# SmartUrometer_Schematic.net
KiCad netlist of a schematic drawn in Altium Designer
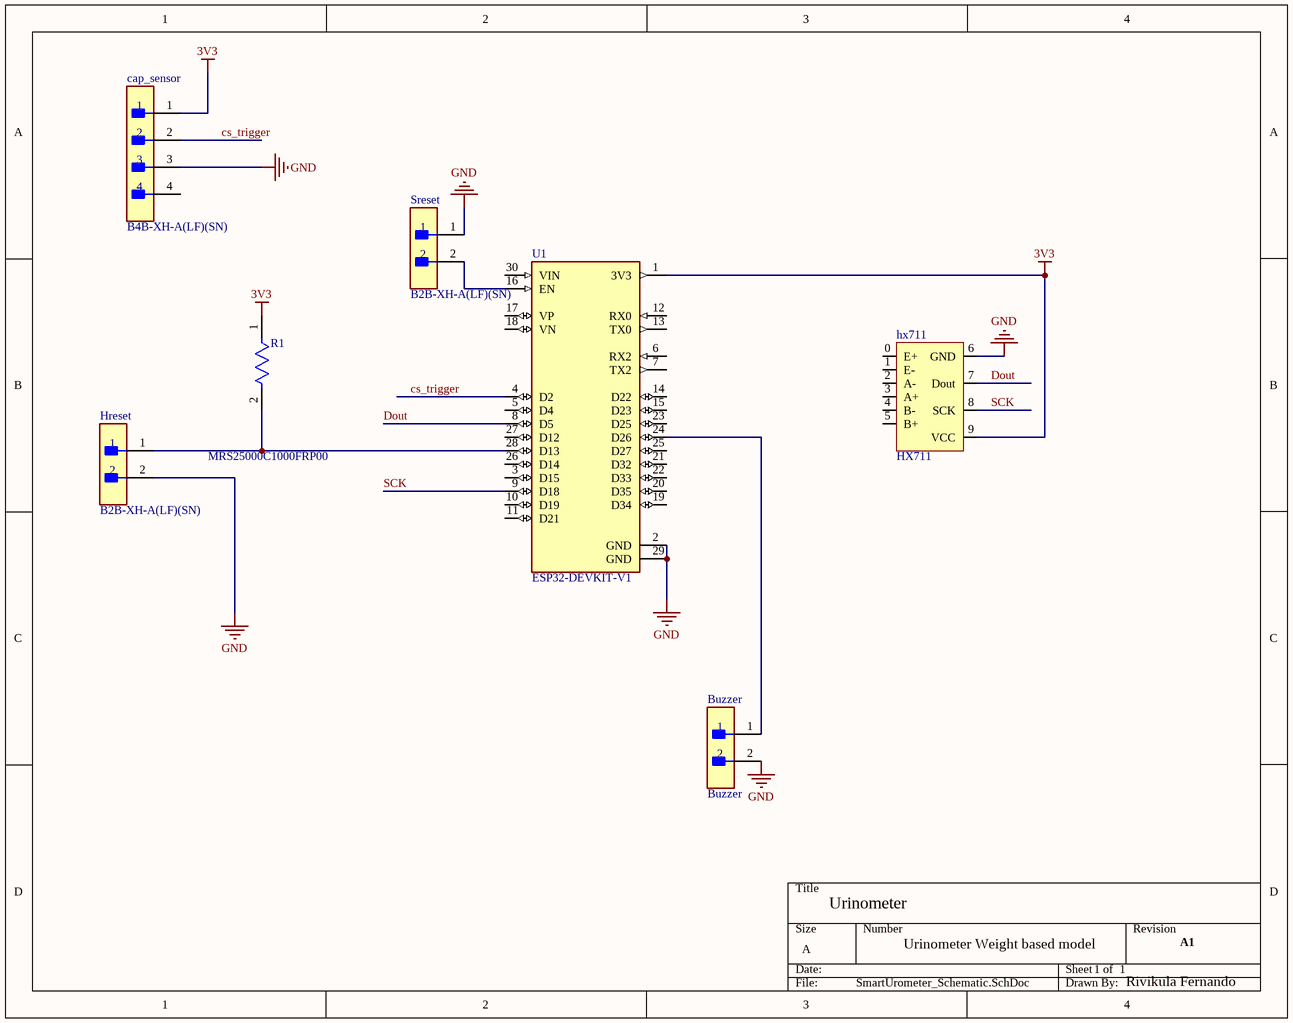
[diagram p0: SmartUrometer_Schematic.SchDoc]

(export (version "E")
  (design (tool "Eeschema 10.0.6"))
  (components
    (comp (ref "Buzzer")
      (value "Buzzer")
      (footprint "FP-B2B-XH-A_LF_SN-MFG")
      (description "CONN HEADER VERT 2POS 2.5MM")
      (libsource (lib "Altium Content Vault") (part "3bc925449376181038e59eaffc5286c"))
    )
    (comp (ref "cap_sensor")
      (value "B4B-XH-A(LF)(SN)")
      (footprint "FP-B4B-XH-A_LF_SN-MFG")
      (description "CONN HEADER VERT 4POS 2.5MM")
      (libsource (lib "Altium Content Vault") (part "299a8cea1bdcbc3624fe62c390fa72c"))
    )
    (comp (ref "Hreset")
      (value "B2B-XH-A(LF)(SN)")
      (footprint "FP-B2B-XH-A_LF_SN-MFG")
      (description "CONN HEADER VERT 2POS 2.5MM")
      (libsource (lib "Altium Content Vault") (part "3bc925449376181038e59eaffc5286c"))
    )
    (comp (ref "hx711") (value "HX711") (footprint "hX711") (libsource (lib "Sensors") (part "HX711")))
    (comp (ref "R1")
      (value "MRS25000C1000FRP00")
      (footprint "FP-MRS25-MFG")
      (fields (field (name "TOLERANCE") "1%"))
      (libsource (lib "Altium Content Vault") (part "1029c3af85768c4190bb7ad29bc67b5"))
    )
    (comp (ref "Sreset")
      (value "B2B-XH-A(LF)(SN)")
      (footprint "FP-B2B-XH-A_LF_SN-MFG")
      (description "CONN HEADER VERT 2POS 2.5MM")
      (libsource (lib "Altium Content Vault") (part "3bc925449376181038e59eaffc5286c"))
    )
    (comp (ref "U1")
      (value "ESP32-DEVKIT-V1")
      (footprint "MODULE_ESP32_DEVKIT_V1")
      (fields (field (name "MF") "Do it"))
      (libsource (lib "Universirty of Moratuwa") (part "ESP32-DEVKIT-V1"))
    )
  )
  (nets
    (net (code "1") (name "/Dout") (class "Default")
      (node (ref "U1") (pin "8") (pinfunction "D5_8") (pintype "bidirectional"))
      (node (ref "hx711") (pin "7") (pinfunction "Dout_7") (pintype "passive"))
    )
    (net (code "2") (name "/SCK") (class "Default")
      (node (ref "U1") (pin "9") (pinfunction "D18_9") (pintype "bidirectional"))
      (node (ref "hx711") (pin "8") (pinfunction "SCK_8") (pintype "passive"))
    )
    (net (code "3") (name "/cs_trigger") (class "Default")
      (node (ref "U1") (pin "4") (pinfunction "D2_4") (pintype "bidirectional"))
      (node (ref "cap_sensor") (pin "2") (pinfunction "2_2") (pintype "passive"))
    )
    (net (code "4") (name "3V3") (class "Default")
      (node (ref "R1") (pin "1") (pinfunction "1_1") (pintype "passive"))
      (node (ref "U1") (pin "1") (pinfunction "3V3_1") (pintype "output"))
      (node (ref "cap_sensor") (pin "1") (pinfunction "1_1") (pintype "passive"))
      (node (ref "hx711") (pin "9") (pinfunction "VCC_9") (pintype "passive"))
    )
    (net (code "5") (name "GND") (class "Default")
      (node (ref "Buzzer") (pin "2") (pinfunction "2_2") (pintype "passive"))
      (node (ref "Hreset") (pin "2") (pinfunction "2_2") (pintype "passive"))
      (node (ref "Sreset") (pin "1") (pinfunction "1_1") (pintype "passive"))
      (node (ref "U1") (pin "2") (pinfunction "GND_2") (pintype "power_in"))
      (node (ref "U1") (pin "29") (pinfunction "GND_29") (pintype "power_in"))
      (node (ref "cap_sensor") (pin "3") (pinfunction "3_3") (pintype "passive"))
      (node (ref "hx711") (pin "6") (pinfunction "GND_6") (pintype "passive"))
    )
    (net (code "6") (name "Net-(U1-D13)") (class "Default")
      (node (ref "Hreset") (pin "1") (pinfunction "1_1") (pintype "passive"))
      (node (ref "R1") (pin "2") (pinfunction "2_2") (pintype "passive"))
      (node (ref "U1") (pin "28") (pinfunction "D13_28") (pintype "bidirectional"))
    )
    (net (code "7") (name "Net-(U1-D26)") (class "Default")
      (node (ref "Buzzer") (pin "1") (pinfunction "1_1") (pintype "passive"))
      (node (ref "U1") (pin "24") (pinfunction "D26_24") (pintype "bidirectional"))
    )
    (net (code "8") (name "Net-(U1-EN)") (class "Default")
      (node (ref "Sreset") (pin "2") (pinfunction "2_2") (pintype "passive"))
      (node (ref "U1") (pin "16") (pinfunction "EN_16") (pintype "input"))
    )
    (net (code "9") (name "unconnected-(U1-D4-Pad5)") (class "Default")
      (node (ref "U1") (pin "5") (pinfunction "D4_5") (pintype "bidirectional"))
    )
    (net (code "10") (name "unconnected-(U1-D12-Pad27)") (class "Default")
      (node (ref "U1") (pin "27") (pinfunction "D12_27") (pintype "bidirectional"))
    )
    (net (code "11") (name "unconnected-(U1-D14-Pad26)") (class "Default")
      (node (ref "U1") (pin "26") (pinfunction "D14_26") (pintype "bidirectional"))
    )
    (net (code "12") (name "unconnected-(U1-D15-Pad3)") (class "Default")
      (node (ref "U1") (pin "3") (pinfunction "D15_3") (pintype "bidirectional"))
    )
    (net (code "13") (name "unconnected-(U1-D19-Pad10)") (class "Default")
      (node (ref "U1") (pin "10") (pinfunction "D19_10") (pintype "bidirectional"))
    )
    (net (code "14") (name "unconnected-(U1-D21-Pad11)") (class "Default")
      (node (ref "U1") (pin "11") (pinfunction "D21_11") (pintype "bidirectional"))
    )
    (net (code "15") (name "unconnected-(U1-D22-Pad14)") (class "Default")
      (node (ref "U1") (pin "14") (pinfunction "D22_14") (pintype "bidirectional"))
    )
    (net (code "16") (name "unconnected-(U1-D23-Pad15)") (class "Default")
      (node (ref "U1") (pin "15") (pinfunction "D23_15") (pintype "bidirectional"))
    )
    (net (code "17") (name "unconnected-(U1-D25-Pad23)") (class "Default")
      (node (ref "U1") (pin "23") (pinfunction "D25_23") (pintype "bidirectional"))
    )
    (net (code "18") (name "unconnected-(U1-D27-Pad25)") (class "Default")
      (node (ref "U1") (pin "25") (pinfunction "D27_25") (pintype "bidirectional"))
    )
    (net (code "19") (name "unconnected-(U1-D32-Pad21)") (class "Default")
      (node (ref "U1") (pin "21") (pinfunction "D32_21") (pintype "bidirectional"))
    )
    (net (code "20") (name "unconnected-(U1-D33-Pad22)") (class "Default")
      (node (ref "U1") (pin "22") (pinfunction "D33_22") (pintype "bidirectional"))
    )
    (net (code "21") (name "unconnected-(U1-D34-Pad19)") (class "Default")
      (node (ref "U1") (pin "19") (pinfunction "D34_19") (pintype "bidirectional"))
    )
    (net (code "22") (name "unconnected-(U1-D35-Pad20)") (class "Default")
      (node (ref "U1") (pin "20") (pinfunction "D35_20") (pintype "bidirectional"))
    )
    (net (code "23") (name "unconnected-(U1-RX0-Pad12)") (class "Default")
      (node (ref "U1") (pin "12") (pinfunction "RX0_12") (pintype "input"))
    )
    (net (code "24") (name "unconnected-(U1-RX2-Pad6)") (class "Default")
      (node (ref "U1") (pin "6") (pinfunction "RX2_6") (pintype "input"))
    )
    (net (code "25") (name "unconnected-(U1-TX0-Pad13)") (class "Default")
      (node (ref "U1") (pin "13") (pinfunction "TX0_13") (pintype "output"))
    )
    (net (code "26") (name "unconnected-(U1-TX2-Pad7)") (class "Default")
      (node (ref "U1") (pin "7") (pinfunction "TX2_7") (pintype "output"))
    )
    (net (code "27") (name "unconnected-(U1-VIN-Pad30)") (class "Default")
      (node (ref "U1") (pin "30") (pinfunction "VIN_30") (pintype "input"))
    )
    (net (code "28") (name "unconnected-(U1-VN-Pad18)") (class "Default")
      (node (ref "U1") (pin "18") (pinfunction "VN_18") (pintype "bidirectional"))
    )
    (net (code "29") (name "unconnected-(U1-VP-Pad17)") (class "Default")
      (node (ref "U1") (pin "17") (pinfunction "VP_17") (pintype "bidirectional"))
    )
    (net (code "30") (name "unconnected-(cap_sensor-Pad4)") (class "Default")
      (node (ref "cap_sensor") (pin "4") (pinfunction "4_4") (pintype "passive"))
    )
    (net (code "31") (name "unconnected-(hx711-A+-Pad3)") (class "Default")
      (node (ref "hx711") (pin "3") (pinfunction "A+_3") (pintype "passive"))
    )
    (net (code "32") (name "unconnected-(hx711-A--Pad2)") (class "Default")
      (node (ref "hx711") (pin "2") (pinfunction "A-_2") (pintype "passive"))
    )
    (net (code "33") (name "unconnected-(hx711-B+-Pad5)") (class "Default")
      (node (ref "hx711") (pin "5") (pinfunction "B+_5") (pintype "passive"))
    )
    (net (code "34") (name "unconnected-(hx711-B--Pad4)") (class "Default")
      (node (ref "hx711") (pin "4") (pinfunction "B-_4") (pintype "passive"))
    )
    (net (code "35") (name "unconnected-(hx711-E+-Pad0)") (class "Default")
      (node (ref "hx711") (pin "0") (pinfunction "E+_0") (pintype "passive"))
    )
    (net (code "36") (name "unconnected-(hx711-E--Pad1)") (class "Default")
      (node (ref "hx711") (pin "1") (pinfunction "E-_1") (pintype "passive"))
    )
  )
)
